# new_and_improved_board.net
KiCad netlist of a schematic drawn in EAGLE
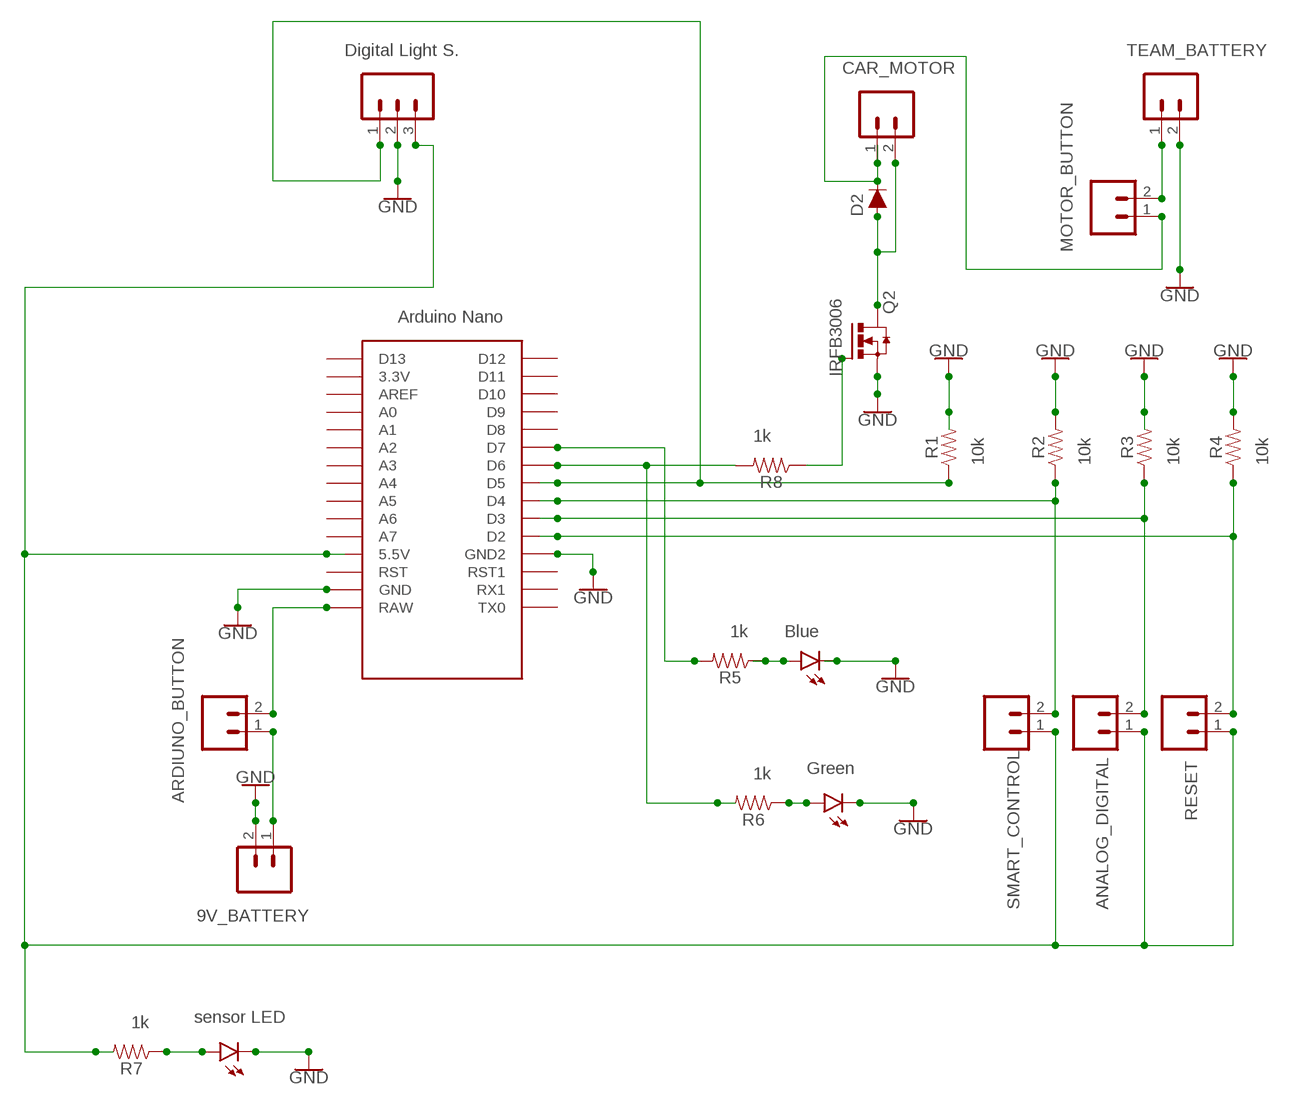
[diagram p0: schematic, sheet 1]

(export (version "E")
  (design (tool "Eeschema 10.0.6"))
  (components
    (comp (ref "D2")
      (value "200mA/100V/1V")
      (footprint "eagle-import:DIODE-1N4148")
      (libsource (lib "eagle-import") (part "DIODE-1N4148"))
    )
    (comp (ref "D4")
      (value "LED3MM")
      (footprint "eagle-import:LED_3MM")
      (fields (field (name "PROD_ID") "DIO-08794") (field (name "PROD_ID_1") "Blue"))
      (libsource (lib "eagle-import") (part "LED3MM"))
    )
    (comp (ref "D5")
      (value "LED3MM")
      (footprint "eagle-import:LED_3MM")
      (fields (field (name "PROD_ID") "DIO-08794") (field (name "PROD_ID_1") "Green"))
      (libsource (lib "eagle-import") (part "LED3MM"))
    )
    (comp (ref "D6")
      (value "LED3MM")
      (footprint "eagle-import:LED_3MM")
      (fields (field (name "PROD_ID") "DIO-08794") (field (name "PROD_ID_1") "sensor LED"))
      (libsource (lib "eagle-import") (part "LED3MM"))
    )
    (comp (ref "J1")
      (value "CONN_02")
      (footprint "eagle-import:1X02")
      (libsource (lib "eagle-import") (part "CONN_02"))
    )
    (comp (ref "J2")
      (value "CONN_02")
      (footprint "eagle-import:1X02")
      (libsource (lib "eagle-import") (part "CONN_02"))
    )
    (comp (ref "J3")
      (value "CONN_02")
      (footprint "eagle-import:1X02")
      (libsource (lib "eagle-import") (part "CONN_02"))
    )
    (comp (ref "J4")
      (value "455-1750-1-ND")
      (footprint "eagle-import:1X03")
      (fields (field (name "PROD_ID") "XXX-00000") (field (name "PROD_ID_1") "Digital Light S."))
      (libsource (lib "eagle-import") (part "CONN_03"))
    )
    (comp (ref "Q2")
      (value "IRF3704L-V")
      (footprint "eagle-import:TO262-V")
      (fields (field (name "POPULARITY") "2") (field (name "POPULARITY_1") "IRFB3006"))
      (libsource (lib "eagle-import") (part "IRF3704L-V"))
    )
    (comp (ref "R1")
      (value "1M")
      (footprint "eagle-import:AXIAL-0.3")
      (fields (field (name "PROD_ID") "RES-09559") (field (name "PROD_ID_1") "10k"))
      (libsource (lib "eagle-import") (part "1MOHM-HORIZ-1/6W-5%"))
    )
    (comp (ref "R2")
      (value "1M")
      (footprint "eagle-import:AXIAL-0.3")
      (fields (field (name "PROD_ID") "RES-09559") (field (name "PROD_ID_1") "10k"))
      (libsource (lib "eagle-import") (part "1MOHM-HORIZ-1/6W-5%"))
    )
    (comp (ref "R3")
      (value "1M")
      (footprint "eagle-import:AXIAL-0.3")
      (fields (field (name "PROD_ID") "RES-09559") (field (name "PROD_ID_1") "10k"))
      (libsource (lib "eagle-import") (part "1MOHM-HORIZ-1/6W-5%"))
    )
    (comp (ref "R4")
      (value "1M")
      (footprint "eagle-import:AXIAL-0.3")
      (fields (field (name "PROD_ID") "RES-09559") (field (name "PROD_ID_1") "10k"))
      (libsource (lib "eagle-import") (part "1MOHM-HORIZ-1/6W-5%"))
    )
    (comp (ref "R5")
      (value "1M")
      (footprint "eagle-import:AXIAL-0.3")
      (fields (field (name "PROD_ID") "RES-09559") (field (name "PROD_ID_1") "1k"))
      (libsource (lib "eagle-import") (part "1MOHM-HORIZ-1/6W-5%"))
    )
    (comp (ref "R6")
      (value "1M")
      (footprint "eagle-import:AXIAL-0.3")
      (fields (field (name "PROD_ID") "RES-09559") (field (name "PROD_ID_1") "1k"))
      (libsource (lib "eagle-import") (part "1MOHM-HORIZ-1/6W-5%"))
    )
    (comp (ref "R7")
      (value "1M")
      (footprint "eagle-import:AXIAL-0.3")
      (fields (field (name "PROD_ID") "RES-09559") (field (name "PROD_ID_1") "1k"))
      (libsource (lib "eagle-import") (part "1MOHM-HORIZ-1/6W-5%"))
    )
    (comp (ref "R8")
      (value "1M")
      (footprint "eagle-import:AXIAL-0.3")
      (fields (field (name "PROD_ID") "RES-09559") (field (name "PROD_ID_1") "1k"))
      (libsource (lib "eagle-import") (part "1MOHM-HORIZ-1/6W-5%"))
    )
    (comp (ref "S1")
      (value "CONN_02")
      (footprint "eagle-import:1X02")
      (libsource (lib "eagle-import") (part "CONN_02"))
    )
    (comp (ref "S2")
      (value "CONN_02")
      (footprint "eagle-import:1X02")
      (libsource (lib "eagle-import") (part "CONN_02"))
    )
    (comp (ref "S3")
      (value "CONN_02")
      (footprint "eagle-import:1X02")
      (libsource (lib "eagle-import") (part "CONN_02"))
    )
    (comp (ref "S4")
      (value "CONN_02")
      (footprint "eagle-import:1X02")
      (libsource (lib "eagle-import") (part "CONN_02"))
    )
    (comp (ref "S5")
      (value "CONN_02")
      (footprint "eagle-import:1X02")
      (libsource (lib "eagle-import") (part "CONN_02"))
    )
    (comp (ref "U$1")
      (value "NANO")
      (footprint "eagle-import:NANO")
      (libsource (lib "eagle-import") (part "NANO"))
    )
  )
  (nets
    (net (code "1") (name "GND") (class "Default")
      (node (ref "D4") (pin "K") (pinfunction "C_K") (pintype "passive"))
      (node (ref "D5") (pin "K") (pinfunction "C_K") (pintype "passive"))
      (node (ref "D6") (pin "K") (pinfunction "C_K") (pintype "passive"))
      (node (ref "J2") (pin "2") (pinfunction "2_2") (pintype "passive"))
      (node (ref "J3") (pin "2") (pinfunction "2_2") (pintype "passive"))
      (node (ref "J4") (pin "2") (pinfunction "2_2") (pintype "passive"))
      (node (ref "Q2") (pin "3") (pinfunction "S_3") (pintype "passive"))
      (node (ref "R1") (pin "P$2") (pinfunction "2_P$2") (pintype "passive"))
      (node (ref "R2") (pin "P$2") (pinfunction "2_P$2") (pintype "passive"))
      (node (ref "R3") (pin "P$2") (pinfunction "2_P$2") (pintype "passive"))
      (node (ref "R4") (pin "P$2") (pinfunction "2_P$2") (pintype "passive"))
      (node (ref "U$1") (pin "GND") (pinfunction "GND_GND") (pintype "bidirectional"))
      (node (ref "U$1") (pin "GND1") (pinfunction "GND2_GND1") (pintype "bidirectional"))
    )
    (net (code "2") (name "Net-(D2-PadC)") (class "Default")
      (node (ref "D2") (pin "C") (pinfunction "C_C") (pintype "passive"))
      (node (ref "J1") (pin "1") (pinfunction "1_1") (pintype "passive"))
      (node (ref "S3") (pin "1") (pinfunction "1_1") (pintype "passive"))
    )
    (net (code "3") (name "Net-(J2-Pad1)") (class "Default")
      (node (ref "J2") (pin "1") (pinfunction "1_1") (pintype "passive"))
      (node (ref "S1") (pin "1") (pinfunction "1_1") (pintype "passive"))
    )
    (net (code "4") (name "Net-(J3-Pad1)") (class "Default")
      (node (ref "J3") (pin "1") (pinfunction "1_1") (pintype "passive"))
      (node (ref "S3") (pin "2") (pinfunction "2_2") (pintype "passive"))
    )
    (net (code "5") (name "Net-(Q2-D)") (class "Default")
      (node (ref "D2") (pin "A") (pinfunction "A_A") (pintype "passive"))
      (node (ref "J1") (pin "2") (pinfunction "2_2") (pintype "passive"))
      (node (ref "Q2") (pin "2") (pinfunction "D_2") (pintype "passive"))
    )
    (net (code "6") (name "Net-(Q2-G)") (class "Default")
      (node (ref "Q2") (pin "1") (pinfunction "G_1") (pintype "passive"))
      (node (ref "R8") (pin "P$1") (pinfunction "1_P$1") (pintype "passive"))
    )
    (net (code "7") (name "Net-(R1-1)") (class "Default")
      (node (ref "J4") (pin "1") (pinfunction "1_1") (pintype "passive"))
      (node (ref "R1") (pin "P$1") (pinfunction "1_P$1") (pintype "passive"))
      (node (ref "U$1") (pin "D5") (pinfunction "D5_D5") (pintype "bidirectional"))
    )
    (net (code "8") (name "Net-(R2-1)") (class "Default")
      (node (ref "R2") (pin "P$1") (pinfunction "1_P$1") (pintype "passive"))
      (node (ref "S2") (pin "2") (pinfunction "2_2") (pintype "passive"))
      (node (ref "U$1") (pin "D4") (pinfunction "D4_D4") (pintype "bidirectional"))
    )
    (net (code "9") (name "Net-(R3-1)") (class "Default")
      (node (ref "R3") (pin "P$1") (pinfunction "1_P$1") (pintype "passive"))
      (node (ref "S4") (pin "2") (pinfunction "2_2") (pintype "passive"))
      (node (ref "U$1") (pin "D3") (pinfunction "D3_D3") (pintype "bidirectional"))
    )
    (net (code "10") (name "Net-(R4-1)") (class "Default")
      (node (ref "R4") (pin "P$1") (pinfunction "1_P$1") (pintype "passive"))
      (node (ref "S5") (pin "2") (pinfunction "2_2") (pintype "passive"))
      (node (ref "U$1") (pin "D2") (pinfunction "D2_D2") (pintype "bidirectional"))
    )
    (net (code "11") (name "Net-(R5-1)") (class "Default")
      (node (ref "D4") (pin "A") (pinfunction "A_A") (pintype "passive"))
      (node (ref "R5") (pin "P$1") (pinfunction "1_P$1") (pintype "passive"))
    )
    (net (code "12") (name "Net-(R5-2)") (class "Default")
      (node (ref "R5") (pin "P$2") (pinfunction "2_P$2") (pintype "passive"))
      (node (ref "U$1") (pin "D7") (pinfunction "D7_D7") (pintype "bidirectional"))
    )
    (net (code "13") (name "Net-(R6-1)") (class "Default")
      (node (ref "D5") (pin "A") (pinfunction "A_A") (pintype "passive"))
      (node (ref "R6") (pin "P$1") (pinfunction "1_P$1") (pintype "passive"))
    )
    (net (code "14") (name "Net-(R6-2)") (class "Default")
      (node (ref "R6") (pin "P$2") (pinfunction "2_P$2") (pintype "passive"))
      (node (ref "R8") (pin "P$2") (pinfunction "2_P$2") (pintype "passive"))
      (node (ref "U$1") (pin "D6") (pinfunction "D6_D6") (pintype "bidirectional"))
    )
    (net (code "15") (name "Net-(R7-1)") (class "Default")
      (node (ref "D6") (pin "A") (pinfunction "A_A") (pintype "passive"))
      (node (ref "R7") (pin "P$1") (pinfunction "1_P$1") (pintype "passive"))
    )
    (net (code "16") (name "Net-(R7-2)") (class "Default")
      (node (ref "J4") (pin "3") (pinfunction "3_3") (pintype "passive"))
      (node (ref "R7") (pin "P$2") (pinfunction "2_P$2") (pintype "passive"))
      (node (ref "S2") (pin "1") (pinfunction "1_1") (pintype "passive"))
      (node (ref "S4") (pin "1") (pinfunction "1_1") (pintype "passive"))
      (node (ref "S5") (pin "1") (pinfunction "1_1") (pintype "passive"))
      (node (ref "U$1") (pin "5V") (pinfunction "5.5V_5V") (pintype "bidirectional"))
    )
    (net (code "17") (name "Net-(S1-Pad2)") (class "Default")
      (node (ref "S1") (pin "2") (pinfunction "2_2") (pintype "passive"))
      (node (ref "U$1") (pin "RAW") (pinfunction "RAW_RAW") (pintype "bidirectional"))
    )
    (net (code "18") (name "unconnected-(U$1-Pad3.3V)") (class "Default")
      (node (ref "U$1") (pin "3.3V") (pinfunction "3.3V_3.3V") (pintype "bidirectional"))
    )
    (net (code "19") (name "unconnected-(U$1-PadA0)") (class "Default")
      (node (ref "U$1") (pin "A0") (pinfunction "A0_A0") (pintype "bidirectional"))
    )
    (net (code "20") (name "unconnected-(U$1-PadA1)") (class "Default")
      (node (ref "U$1") (pin "A1") (pinfunction "A1_A1") (pintype "bidirectional"))
    )
    (net (code "21") (name "unconnected-(U$1-PadA2)") (class "Default")
      (node (ref "U$1") (pin "A2") (pinfunction "A2_A2") (pintype "bidirectional"))
    )
    (net (code "22") (name "unconnected-(U$1-PadA3)") (class "Default")
      (node (ref "U$1") (pin "A3") (pinfunction "A3_A3") (pintype "bidirectional"))
    )
    (net (code "23") (name "unconnected-(U$1-PadA4)") (class "Default")
      (node (ref "U$1") (pin "A4") (pinfunction "A4_A4") (pintype "bidirectional"))
    )
    (net (code "24") (name "unconnected-(U$1-PadA5)") (class "Default")
      (node (ref "U$1") (pin "A5") (pinfunction "A5_A5") (pintype "bidirectional"))
    )
    (net (code "25") (name "unconnected-(U$1-PadA6)") (class "Default")
      (node (ref "U$1") (pin "A6") (pinfunction "A6_A6") (pintype "bidirectional"))
    )
    (net (code "26") (name "unconnected-(U$1-PadA7)") (class "Default")
      (node (ref "U$1") (pin "A7") (pinfunction "A7_A7") (pintype "bidirectional"))
    )
    (net (code "27") (name "unconnected-(U$1-PadAREF)") (class "Default")
      (node (ref "U$1") (pin "AREF") (pinfunction "AREF_AREF") (pintype "bidirectional"))
    )
    (net (code "28") (name "unconnected-(U$1-PadD8)") (class "Default")
      (node (ref "U$1") (pin "D8") (pinfunction "D8_D8") (pintype "bidirectional"))
    )
    (net (code "29") (name "unconnected-(U$1-PadD9)") (class "Default")
      (node (ref "U$1") (pin "D9") (pinfunction "D9_D9") (pintype "bidirectional"))
    )
    (net (code "30") (name "unconnected-(U$1-PadD10)") (class "Default")
      (node (ref "U$1") (pin "D10") (pinfunction "D10_D10") (pintype "bidirectional"))
    )
    (net (code "31") (name "unconnected-(U$1-PadD11)") (class "Default")
      (node (ref "U$1") (pin "D11") (pinfunction "D11_D11") (pintype "bidirectional"))
    )
    (net (code "32") (name "unconnected-(U$1-PadD12)") (class "Default")
      (node (ref "U$1") (pin "D12") (pinfunction "D12_D12") (pintype "bidirectional"))
    )
    (net (code "33") (name "unconnected-(U$1-PadD13)") (class "Default")
      (node (ref "U$1") (pin "D13") (pinfunction "D13_D13") (pintype "bidirectional"))
    )
    (net (code "34") (name "unconnected-(U$1-PadICSP1)") (class "Default")
      (node (ref "U$1") (pin "ICSP1") (pinfunction "ICSP1_ICSP1") (pintype "bidirectional"))
    )
    (net (code "35") (name "unconnected-(U$1-PadICSP2)") (class "Default")
      (node (ref "U$1") (pin "ICSP2") (pinfunction "ICSP2_ICSP2") (pintype "bidirectional"))
    )
    (net (code "36") (name "unconnected-(U$1-PadICSP3)") (class "Default")
      (node (ref "U$1") (pin "ICSP3") (pinfunction "ICSP3_ICSP3") (pintype "bidirectional"))
    )
    (net (code "37") (name "unconnected-(U$1-PadICSP4)") (class "Default")
      (node (ref "U$1") (pin "ICSP4") (pinfunction "ICSP4_ICSP4") (pintype "bidirectional"))
    )
    (net (code "38") (name "unconnected-(U$1-PadICSP5)") (class "Default")
      (node (ref "U$1") (pin "ICSP5") (pinfunction "ICSP5_ICSP5") (pintype "bidirectional"))
    )
    (net (code "39") (name "unconnected-(U$1-PadICSP6)") (class "Default")
      (node (ref "U$1") (pin "ICSP6") (pinfunction "ICSP6_ICSP6") (pintype "bidirectional"))
    )
    (net (code "40") (name "unconnected-(U$1-PadRST)") (class "Default")
      (node (ref "U$1") (pin "RST") (pinfunction "RST_RST") (pintype "bidirectional"))
    )
    (net (code "41") (name "unconnected-(U$1-PadRST1)") (class "Default")
      (node (ref "U$1") (pin "RST1") (pinfunction "RST1_RST1") (pintype "bidirectional"))
    )
    (net (code "42") (name "unconnected-(U$1-PadRX1)") (class "Default")
      (node (ref "U$1") (pin "RX1") (pinfunction "RX1_RX1") (pintype "bidirectional"))
    )
    (net (code "43") (name "unconnected-(U$1-PadTX0)") (class "Default")
      (node (ref "U$1") (pin "TX0") (pinfunction "TX0_TX0") (pintype "bidirectional"))
    )
  )
)
